# FrameworkGPU_to_MXM.net
KiCad netlist of a schematic drawn in EasyEDA Pro
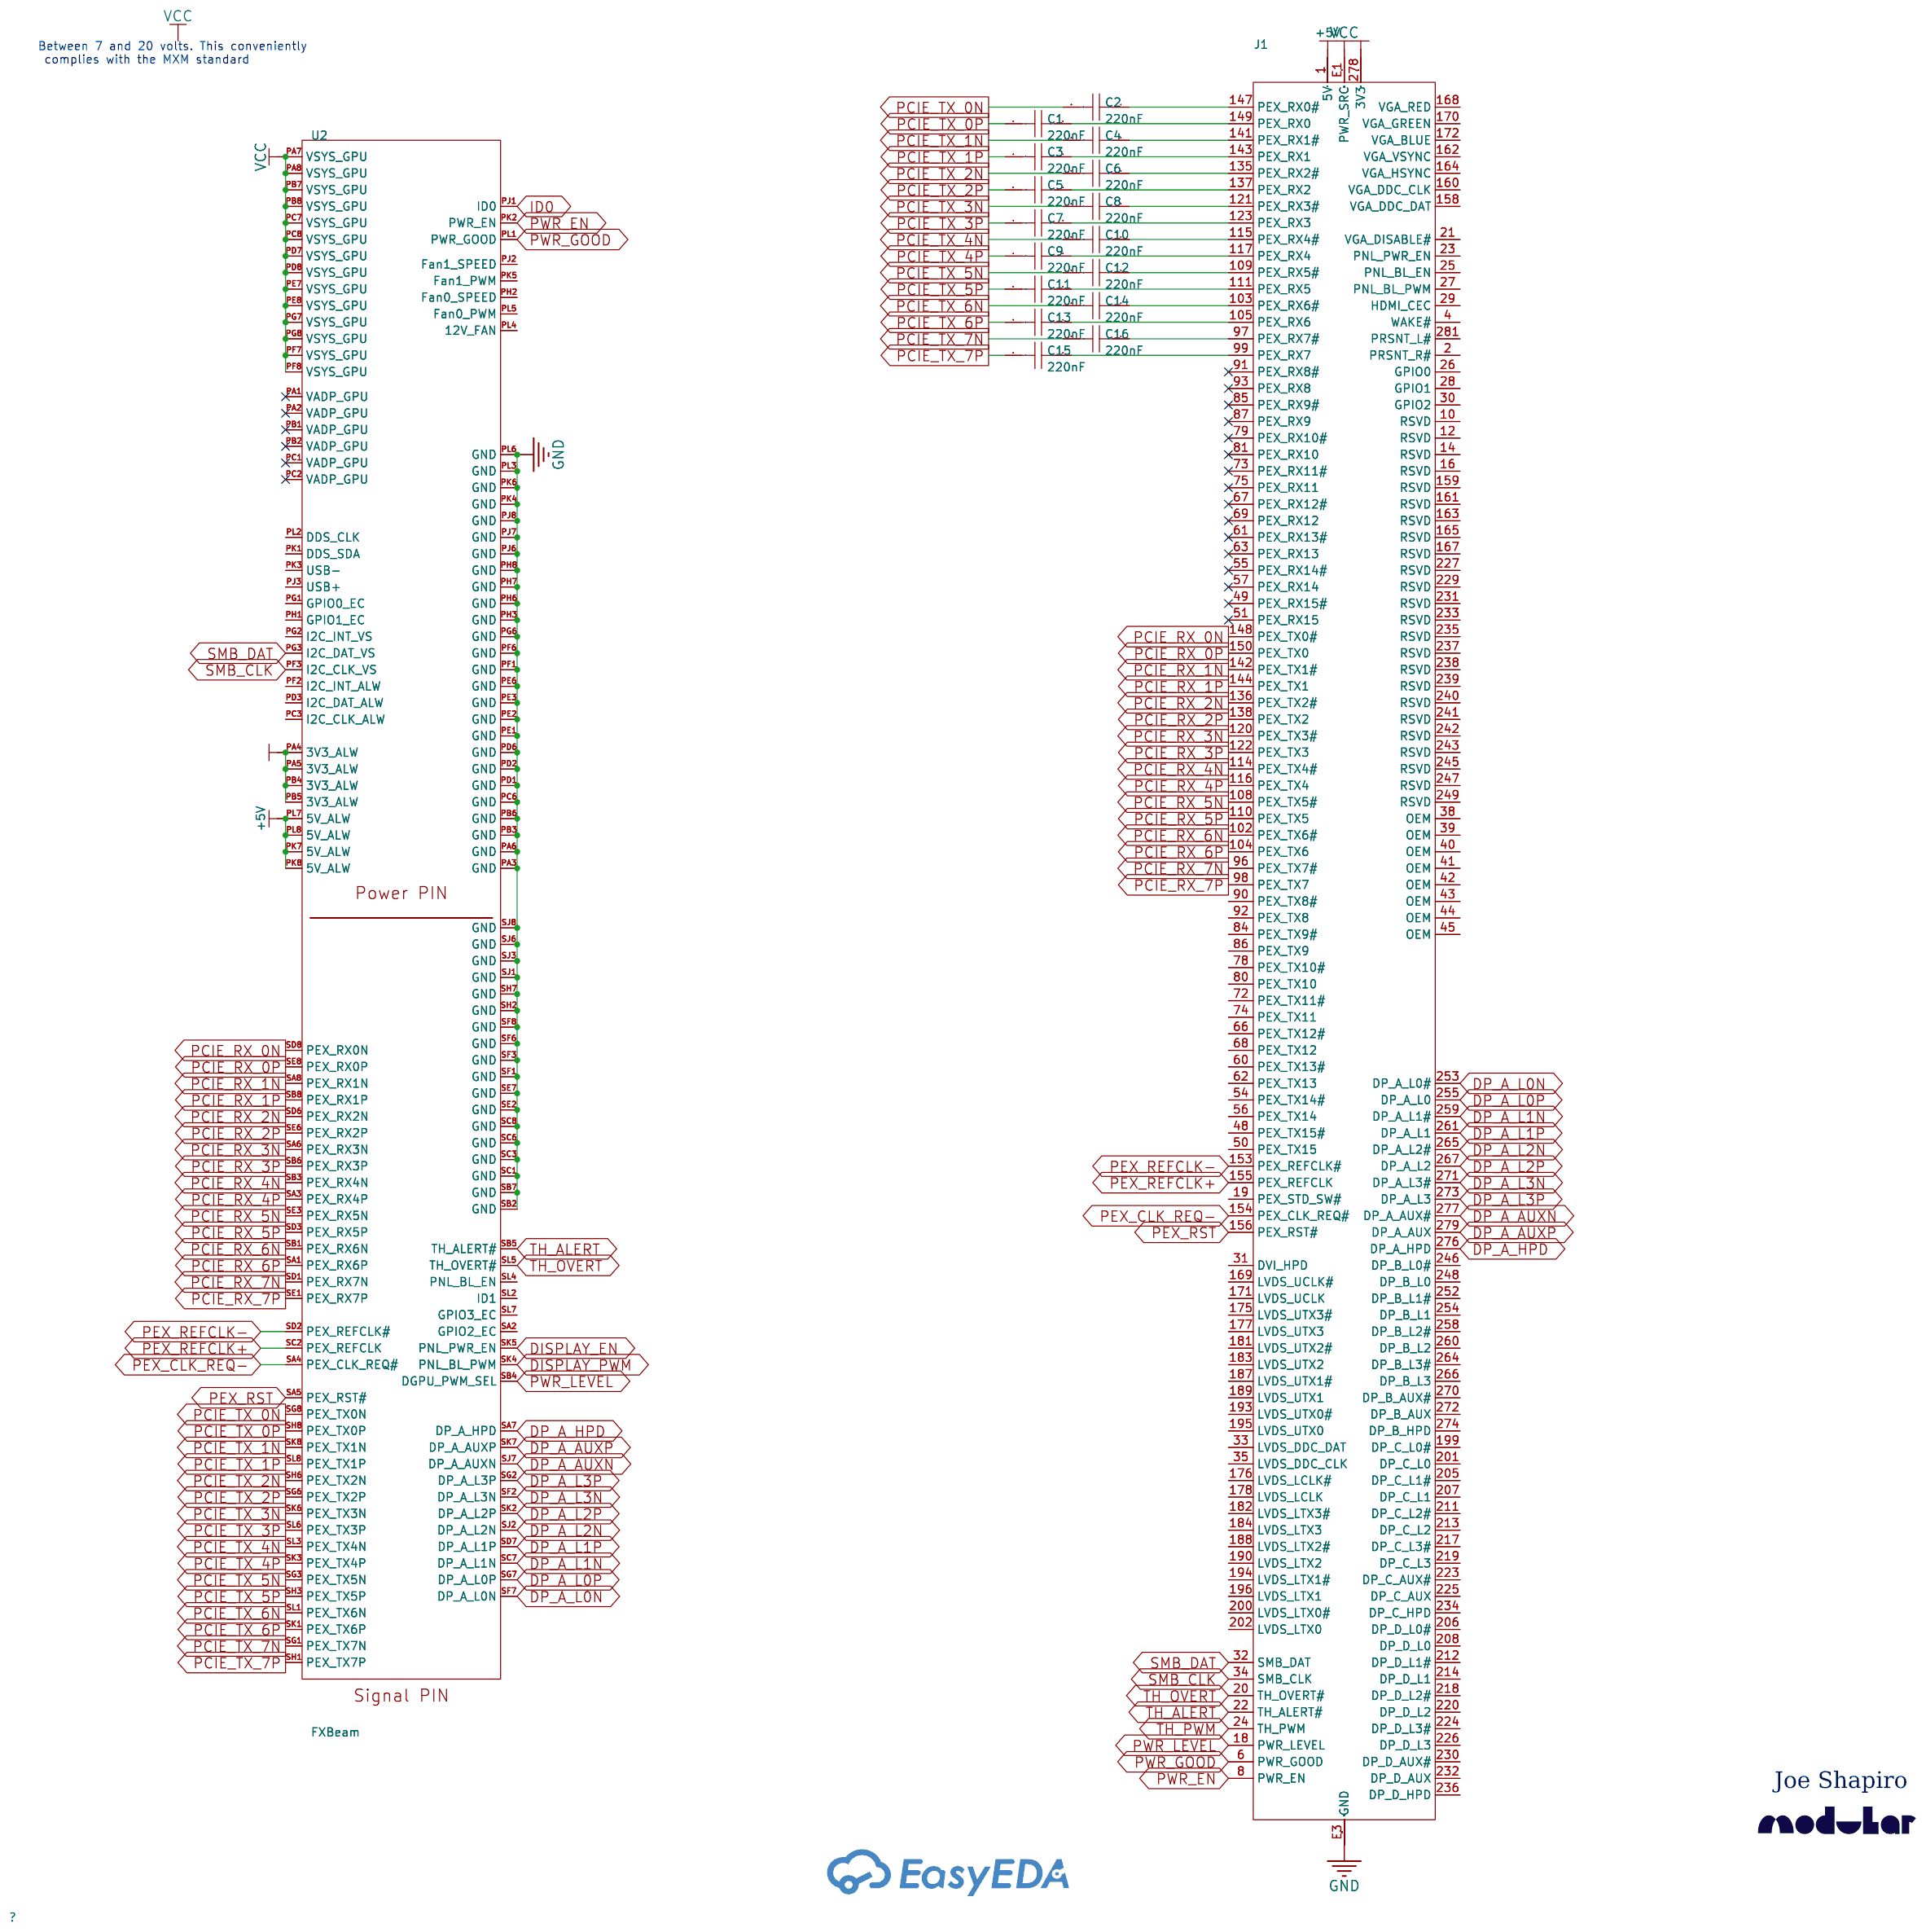
[diagram p0: schematic sheet]

(export (version "E")
  (design (tool "Eeschema 10.0.6"))
  (components
    (comp (ref "C1")
      (value "220nF")
      (footprint "easyedapro:C0603")
      (libsource (lib "easyedapro") (part "CAP"))
    )
    (comp (ref "C2")
      (value "220nF")
      (footprint "easyedapro:C0603")
      (libsource (lib "easyedapro") (part "CAP"))
    )
    (comp (ref "C3")
      (value "220nF")
      (footprint "easyedapro:C0603")
      (libsource (lib "easyedapro") (part "CAP"))
    )
    (comp (ref "C4")
      (value "220nF")
      (footprint "easyedapro:C0603")
      (libsource (lib "easyedapro") (part "CAP"))
    )
    (comp (ref "C5")
      (value "220nF")
      (footprint "easyedapro:C0603")
      (libsource (lib "easyedapro") (part "CAP"))
    )
    (comp (ref "C6")
      (value "220nF")
      (footprint "easyedapro:C0603")
      (libsource (lib "easyedapro") (part "CAP"))
    )
    (comp (ref "C7")
      (value "220nF")
      (footprint "easyedapro:C0603")
      (libsource (lib "easyedapro") (part "CAP"))
    )
    (comp (ref "C8")
      (value "220nF")
      (footprint "easyedapro:C0603")
      (libsource (lib "easyedapro") (part "CAP"))
    )
    (comp (ref "C9")
      (value "220nF")
      (footprint "easyedapro:C0603")
      (libsource (lib "easyedapro") (part "CAP"))
    )
    (comp (ref "C10")
      (value "220nF")
      (footprint "easyedapro:C0603")
      (libsource (lib "easyedapro") (part "CAP"))
    )
    (comp (ref "C11")
      (value "220nF")
      (footprint "easyedapro:C0603")
      (libsource (lib "easyedapro") (part "CAP"))
    )
    (comp (ref "C12")
      (value "220nF")
      (footprint "easyedapro:C0603")
      (libsource (lib "easyedapro") (part "CAP"))
    )
    (comp (ref "C13")
      (value "220nF")
      (footprint "easyedapro:C0603")
      (libsource (lib "easyedapro") (part "CAP"))
    )
    (comp (ref "C14")
      (value "220nF")
      (footprint "easyedapro:C0603")
      (libsource (lib "easyedapro") (part "CAP"))
    )
    (comp (ref "C15")
      (value "220nF")
      (footprint "easyedapro:C0603")
      (libsource (lib "easyedapro") (part "CAP"))
    )
    (comp (ref "C16")
      (value "220nF")
      (footprint "easyedapro:C0603")
      (libsource (lib "easyedapro") (part "CAP"))
    )
    (comp (ref "J1") (value "MXM3.0") (libsource (lib "easyedapro") (part "MXM3.0")))
    (comp (ref "U2") (value "FXBeam") (libsource (lib "easyedapro") (part "FXBeam")))
  )
  (nets
    (net (code "1") (name "+3.3V") (class "Default")
      (node (ref "J1") (pin "278") (pinfunction "3V3_278") (pintype "input"))
      (node (ref "J1") (pin "280") (pinfunction "3V3_280") (pintype "input"))
      (node (ref "U2") (pin "PA4") (pinfunction "3V3_ALW_PA4") (pintype "unspecified"))
      (node (ref "U2") (pin "PA5") (pinfunction "3V3_ALW_PA5") (pintype "unspecified"))
      (node (ref "U2") (pin "PB4") (pinfunction "3V3_ALW_PB4") (pintype "unspecified"))
      (node (ref "U2") (pin "PB5") (pinfunction "3V3_ALW_PB5") (pintype "unspecified"))
    )
    (net (code "2") (name "+5V") (class "Default")
      (node (ref "J1") (pin "1") (pinfunction "5V_1") (pintype "input"))
      (node (ref "J1") (pin "3") (pinfunction "5V_3") (pintype "input"))
      (node (ref "J1") (pin "5") (pinfunction "5V_5") (pintype "input"))
      (node (ref "J1") (pin "7") (pinfunction "5V_7") (pintype "input"))
      (node (ref "J1") (pin "9") (pinfunction "5V_9") (pintype "input"))
      (node (ref "U2") (pin "PK7") (pinfunction "5V_ALW_PK7") (pintype "unspecified"))
      (node (ref "U2") (pin "PK8") (pinfunction "5V_ALW_PK8") (pintype "unspecified"))
      (node (ref "U2") (pin "PL7") (pinfunction "5V_ALW_PL7") (pintype "unspecified"))
      (node (ref "U2") (pin "PL8") (pinfunction "5V_ALW_PL8") (pintype "unspecified"))
    )
    (net (code "3") (name "DISPLAY_EN") (class "Default")
      (node (ref "U2") (pin "SK5") (pinfunction "PNL_PWR_EN_SK5") (pintype "unspecified"))
    )
    (net (code "4") (name "DISPLAY_PWM") (class "Default")
      (node (ref "U2") (pin "SK4") (pinfunction "PNL_BL_PWM_SK4") (pintype "unspecified"))
    )
    (net (code "5") (name "DP_A_AUXN") (class "Default")
      (node (ref "J1") (pin "277") (pinfunction "DP_A_AUX#_277") (pintype "bidirectional"))
      (node (ref "U2") (pin "SJ7") (pinfunction "DP_A_AUXN_SJ7") (pintype "unspecified"))
    )
    (net (code "6") (name "DP_A_AUXP") (class "Default")
      (node (ref "J1") (pin "279") (pinfunction "DP_A_AUX_279") (pintype "bidirectional"))
      (node (ref "U2") (pin "SK7") (pinfunction "DP_A_AUXP_SK7") (pintype "unspecified"))
    )
    (net (code "7") (name "DP_A_HPD") (class "Default")
      (node (ref "J1") (pin "276") (pinfunction "DP_A_HPD_276") (pintype "input"))
      (node (ref "U2") (pin "SA7") (pinfunction "DP_A_HPD_SA7") (pintype "unspecified"))
    )
    (net (code "8") (name "DP_A_L0N") (class "Default")
      (node (ref "J1") (pin "253") (pinfunction "DP_A_L0#_253") (pintype "output"))
      (node (ref "U2") (pin "SF7") (pinfunction "DP_A_L0N_SF7") (pintype "unspecified"))
    )
    (net (code "9") (name "DP_A_L0P") (class "Default")
      (node (ref "J1") (pin "255") (pinfunction "DP_A_L0_255") (pintype "output"))
      (node (ref "U2") (pin "SG7") (pinfunction "DP_A_L0P_SG7") (pintype "unspecified"))
    )
    (net (code "10") (name "DP_A_L1N") (class "Default")
      (node (ref "J1") (pin "259") (pinfunction "DP_A_L1#_259") (pintype "output"))
      (node (ref "U2") (pin "SC7") (pinfunction "DP_A_L1N_SC7") (pintype "unspecified"))
    )
    (net (code "11") (name "DP_A_L1P") (class "Default")
      (node (ref "J1") (pin "261") (pinfunction "DP_A_L1_261") (pintype "output"))
      (node (ref "U2") (pin "SD7") (pinfunction "DP_A_L1P_SD7") (pintype "unspecified"))
    )
    (net (code "12") (name "DP_A_L2N") (class "Default")
      (node (ref "J1") (pin "265") (pinfunction "DP_A_L2#_265") (pintype "output"))
      (node (ref "U2") (pin "SJ2") (pinfunction "DP_A_L2N_SJ2") (pintype "unspecified"))
    )
    (net (code "13") (name "DP_A_L2P") (class "Default")
      (node (ref "J1") (pin "267") (pinfunction "DP_A_L2_267") (pintype "output"))
      (node (ref "U2") (pin "SK2") (pinfunction "DP_A_L2P_SK2") (pintype "unspecified"))
    )
    (net (code "14") (name "DP_A_L3N") (class "Default")
      (node (ref "J1") (pin "271") (pinfunction "DP_A_L3#_271") (pintype "output"))
      (node (ref "U2") (pin "SF2") (pinfunction "DP_A_L3N_SF2") (pintype "unspecified"))
    )
    (net (code "15") (name "DP_A_L3P") (class "Default")
      (node (ref "J1") (pin "273") (pinfunction "DP_A_L3_273") (pintype "output"))
      (node (ref "U2") (pin "SG2") (pinfunction "DP_A_L3P_SG2") (pintype "unspecified"))
    )
    (net (code "16") (name "GND") (class "Default")
      (node (ref "J1") (pin "100") (pinfunction "GND_100") (pintype "input"))
      (node (ref "J1") (pin "101") (pinfunction "GND_101") (pintype "input"))
      (node (ref "J1") (pin "106") (pinfunction "GND_106") (pintype "input"))
      (node (ref "J1") (pin "107") (pinfunction "GND_107") (pintype "input"))
      (node (ref "J1") (pin "11") (pinfunction "GND_11") (pintype "input"))
      (node (ref "J1") (pin "112") (pinfunction "GND_112") (pintype "input"))
      (node (ref "J1") (pin "113") (pinfunction "GND_113") (pintype "input"))
      (node (ref "J1") (pin "118") (pinfunction "GND_118") (pintype "input"))
      (node (ref "J1") (pin "119") (pinfunction "GND_119") (pintype "input"))
      (node (ref "J1") (pin "124") (pinfunction "GND_124") (pintype "input"))
      (node (ref "J1") (pin "125") (pinfunction "GND_125") (pintype "input"))
      (node (ref "J1") (pin "13") (pinfunction "GND_13") (pintype "input"))
      (node (ref "J1") (pin "133") (pinfunction "GND_133") (pintype "input"))
      (node (ref "J1") (pin "134") (pinfunction "GND_134") (pintype "input"))
      (node (ref "J1") (pin "139") (pinfunction "GND_139") (pintype "input"))
      (node (ref "J1") (pin "140") (pinfunction "GND_140") (pintype "input"))
      (node (ref "J1") (pin "145") (pinfunction "GND_145") (pintype "input"))
      (node (ref "J1") (pin "146") (pinfunction "GND_146") (pintype "input"))
      (node (ref "J1") (pin "15") (pinfunction "GND_15") (pintype "input"))
      (node (ref "J1") (pin "151") (pinfunction "GND_151") (pintype "input"))
      (node (ref "J1") (pin "152") (pinfunction "GND_152") (pintype "input"))
      (node (ref "J1") (pin "157") (pinfunction "GND_157") (pintype "input"))
      (node (ref "J1") (pin "166") (pinfunction "GND_166") (pintype "input"))
      (node (ref "J1") (pin "17") (pinfunction "GND_17") (pintype "input"))
      (node (ref "J1") (pin "173") (pinfunction "GND_173") (pintype "input"))
      (node (ref "J1") (pin "174") (pinfunction "GND_174") (pintype "input"))
      (node (ref "J1") (pin "179") (pinfunction "GND_179") (pintype "input"))
      (node (ref "J1") (pin "180") (pinfunction "GND_180") (pintype "input"))
      (node (ref "J1") (pin "185") (pinfunction "GND_185") (pintype "input"))
      (node (ref "J1") (pin "186") (pinfunction "GND_186") (pintype "input"))
      (node (ref "J1") (pin "191") (pinfunction "GND_191") (pintype "input"))
      (node (ref "J1") (pin "192") (pinfunction "GND_192") (pintype "input"))
      (node (ref "J1") (pin "197") (pinfunction "GND_197") (pintype "input"))
      (node (ref "J1") (pin "198") (pinfunction "GND_198") (pintype "input"))
      (node (ref "J1") (pin "203") (pinfunction "GND_203") (pintype "input"))
      (node (ref "J1") (pin "204") (pinfunction "GND_204") (pintype "input"))
      (node (ref "J1") (pin "209") (pinfunction "GND_209") (pintype "input"))
      (node (ref "J1") (pin "210") (pinfunction "GND_210") (pintype "input"))
      (node (ref "J1") (pin "215") (pinfunction "GND_215") (pintype "input"))
      (node (ref "J1") (pin "216") (pinfunction "GND_216") (pintype "input"))
      (node (ref "J1") (pin "221") (pinfunction "GND_221") (pintype "input"))
      (node (ref "J1") (pin "222") (pinfunction "GND_222") (pintype "input"))
      (node (ref "J1") (pin "228") (pinfunction "GND_228") (pintype "input"))
      (node (ref "J1") (pin "244") (pinfunction "GND_244") (pintype "input"))
      (node (ref "J1") (pin "250") (pinfunction "GND_250") (pintype "input"))
      (node (ref "J1") (pin "251") (pinfunction "GND_251") (pintype "input"))
      (node (ref "J1") (pin "256") (pinfunction "GND_256") (pintype "input"))
      (node (ref "J1") (pin "257") (pinfunction "GND_257") (pintype "input"))
      (node (ref "J1") (pin "262") (pinfunction "GND_262") (pintype "input"))
      (node (ref "J1") (pin "263") (pinfunction "GND_263") (pintype "input"))
      (node (ref "J1") (pin "268") (pinfunction "GND_268") (pintype "input"))
      (node (ref "J1") (pin "269") (pinfunction "GND_269") (pintype "input"))
      (node (ref "J1") (pin "275") (pinfunction "GND_275") (pintype "input"))
      (node (ref "J1") (pin "36") (pinfunction "GND_36") (pintype "input"))
      (node (ref "J1") (pin "37") (pinfunction "GND_37") (pintype "input"))
      (node (ref "J1") (pin "46") (pinfunction "GND_46") (pintype "input"))
      (node (ref "J1") (pin "47") (pinfunction "GND_47") (pintype "input"))
      (node (ref "J1") (pin "52") (pinfunction "GND_52") (pintype "input"))
      (node (ref "J1") (pin "53") (pinfunction "GND_53") (pintype "input"))
      (node (ref "J1") (pin "58") (pinfunction "GND_58") (pintype "input"))
      (node (ref "J1") (pin "59") (pinfunction "GND_59") (pintype "input"))
      (node (ref "J1") (pin "64") (pinfunction "GND_64") (pintype "input"))
      (node (ref "J1") (pin "65") (pinfunction "GND_65") (pintype "input"))
      (node (ref "J1") (pin "70") (pinfunction "GND_70") (pintype "input"))
      (node (ref "J1") (pin "71") (pinfunction "GND_71") (pintype "input"))
      (node (ref "J1") (pin "76") (pinfunction "GND_76") (pintype "input"))
      (node (ref "J1") (pin "77") (pinfunction "GND_77") (pintype "input"))
      (node (ref "J1") (pin "82") (pinfunction "GND_82") (pintype "input"))
      (node (ref "J1") (pin "83") (pinfunction "GND_83") (pintype "input"))
      (node (ref "J1") (pin "88") (pinfunction "GND_88") (pintype "input"))
      (node (ref "J1") (pin "89") (pinfunction "GND_89") (pintype "input"))
      (node (ref "J1") (pin "94") (pinfunction "GND_94") (pintype "input"))
      (node (ref "J1") (pin "95") (pinfunction "GND_95") (pintype "input"))
      (node (ref "J1") (pin "E3") (pinfunction "GND_E3") (pintype "input"))
      (node (ref "J1") (pin "E4") (pinfunction "GND_E4") (pintype "input"))
      (node (ref "U2") (pin "PA3") (pinfunction "GND_PA3") (pintype "unspecified"))
      (node (ref "U2") (pin "PA6") (pinfunction "GND_PA6") (pintype "unspecified"))
      (node (ref "U2") (pin "PB3") (pinfunction "GND_PB3") (pintype "unspecified"))
      (node (ref "U2") (pin "PB6") (pinfunction "GND_PB6") (pintype "unspecified"))
      (node (ref "U2") (pin "PC6") (pinfunction "GND_PC6") (pintype "unspecified"))
      (node (ref "U2") (pin "PD1") (pinfunction "GND_PD1") (pintype "unspecified"))
      (node (ref "U2") (pin "PD2") (pinfunction "GND_PD2") (pintype "unspecified"))
      (node (ref "U2") (pin "PD6") (pinfunction "GND_PD6") (pintype "unspecified"))
      (node (ref "U2") (pin "PE1") (pinfunction "GND_PE1") (pintype "unspecified"))
      (node (ref "U2") (pin "PE2") (pinfunction "GND_PE2") (pintype "unspecified"))
      (node (ref "U2") (pin "PE3") (pinfunction "GND_PE3") (pintype "unspecified"))
      (node (ref "U2") (pin "PE6") (pinfunction "GND_PE6") (pintype "unspecified"))
      (node (ref "U2") (pin "PF1") (pinfunction "GND_PF1") (pintype "unspecified"))
      (node (ref "U2") (pin "PF6") (pinfunction "GND_PF6") (pintype "unspecified"))
      (node (ref "U2") (pin "PG6") (pinfunction "GND_PG6") (pintype "unspecified"))
      (node (ref "U2") (pin "PH3") (pinfunction "GND_PH3") (pintype "unspecified"))
      (node (ref "U2") (pin "PH6") (pinfunction "GND_PH6") (pintype "unspecified"))
      (node (ref "U2") (pin "PH7") (pinfunction "GND_PH7") (pintype "unspecified"))
      (node (ref "U2") (pin "PH8") (pinfunction "GND_PH8") (pintype "unspecified"))
      (node (ref "U2") (pin "PJ6") (pinfunction "GND_PJ6") (pintype "unspecified"))
      (node (ref "U2") (pin "PJ7") (pinfunction "GND_PJ7") (pintype "unspecified"))
      (node (ref "U2") (pin "PJ8") (pinfunction "GND_PJ8") (pintype "unspecified"))
      (node (ref "U2") (pin "PK4") (pinfunction "GND_PK4") (pintype "unspecified"))
      (node (ref "U2") (pin "PK6") (pinfunction "GND_PK6") (pintype "unspecified"))
      (node (ref "U2") (pin "PL3") (pinfunction "GND_PL3") (pintype "unspecified"))
      (node (ref "U2") (pin "PL6") (pinfunction "GND_PL6") (pintype "unspecified"))
      (node (ref "U2") (pin "SB2") (pinfunction "GND_SB2") (pintype "unspecified"))
      (node (ref "U2") (pin "SB7") (pinfunction "GND_SB7") (pintype "unspecified"))
      (node (ref "U2") (pin "SC1") (pinfunction "GND_SC1") (pintype "unspecified"))
      (node (ref "U2") (pin "SC3") (pinfunction "GND_SC3") (pintype "unspecified"))
      (node (ref "U2") (pin "SC6") (pinfunction "GND_SC6") (pintype "unspecified"))
      (node (ref "U2") (pin "SC8") (pinfunction "GND_SC8") (pintype "unspecified"))
      (node (ref "U2") (pin "SE2") (pinfunction "GND_SE2") (pintype "unspecified"))
      (node (ref "U2") (pin "SE7") (pinfunction "GND_SE7") (pintype "unspecified"))
      (node (ref "U2") (pin "SF1") (pinfunction "GND_SF1") (pintype "unspecified"))
      (node (ref "U2") (pin "SF3") (pinfunction "GND_SF3") (pintype "unspecified"))
      (node (ref "U2") (pin "SF6") (pinfunction "GND_SF6") (pintype "unspecified"))
      (node (ref "U2") (pin "SF8") (pinfunction "GND_SF8") (pintype "unspecified"))
      (node (ref "U2") (pin "SH2") (pinfunction "GND_SH2") (pintype "unspecified"))
      (node (ref "U2") (pin "SH7") (pinfunction "GND_SH7") (pintype "unspecified"))
      (node (ref "U2") (pin "SJ1") (pinfunction "GND_SJ1") (pintype "unspecified"))
      (node (ref "U2") (pin "SJ3") (pinfunction "GND_SJ3") (pintype "unspecified"))
      (node (ref "U2") (pin "SJ6") (pinfunction "GND_SJ6") (pintype "unspecified"))
      (node (ref "U2") (pin "SJ8") (pinfunction "GND_SJ8") (pintype "unspecified"))
    )
    (net (code "17") (name "ID0") (class "Default")
      (node (ref "U2") (pin "PJ1") (pinfunction "ID0_PJ1") (pintype "output"))
    )
    (net (code "18") (name "Net-(J1-PEX_RX0#)") (class "Default")
      (node (ref "C2") (pin "1") (pinfunction "1_1") (pintype "input"))
      (node (ref "J1") (pin "147") (pinfunction "PEX_RX0#_147") (pintype "output"))
    )
    (net (code "19") (name "Net-(J1-PEX_RX0)") (class "Default")
      (node (ref "C1") (pin "1") (pinfunction "1_1") (pintype "input"))
      (node (ref "J1") (pin "149") (pinfunction "PEX_RX0_149") (pintype "output"))
    )
    (net (code "20") (name "Net-(J1-PEX_RX1#)") (class "Default")
      (node (ref "C4") (pin "1") (pinfunction "1_1") (pintype "input"))
      (node (ref "J1") (pin "141") (pinfunction "PEX_RX1#_141") (pintype "output"))
    )
    (net (code "21") (name "Net-(J1-PEX_RX1)") (class "Default")
      (node (ref "C3") (pin "1") (pinfunction "1_1") (pintype "input"))
      (node (ref "J1") (pin "143") (pinfunction "PEX_RX1_143") (pintype "output"))
    )
    (net (code "22") (name "Net-(J1-PEX_RX2#)") (class "Default")
      (node (ref "C6") (pin "1") (pinfunction "1_1") (pintype "input"))
      (node (ref "J1") (pin "135") (pinfunction "PEX_RX2#_135") (pintype "output"))
    )
    (net (code "23") (name "Net-(J1-PEX_RX2)") (class "Default")
      (node (ref "C5") (pin "1") (pinfunction "1_1") (pintype "input"))
      (node (ref "J1") (pin "137") (pinfunction "PEX_RX2_137") (pintype "output"))
    )
    (net (code "24") (name "Net-(J1-PEX_RX3#)") (class "Default")
      (node (ref "C8") (pin "1") (pinfunction "1_1") (pintype "input"))
      (node (ref "J1") (pin "121") (pinfunction "PEX_RX3#_121") (pintype "output"))
    )
    (net (code "25") (name "Net-(J1-PEX_RX3)") (class "Default")
      (node (ref "C7") (pin "1") (pinfunction "1_1") (pintype "input"))
      (node (ref "J1") (pin "123") (pinfunction "PEX_RX3_123") (pintype "output"))
    )
    (net (code "26") (name "Net-(J1-PEX_RX4#)") (class "Default")
      (node (ref "C10") (pin "1") (pinfunction "1_1") (pintype "input"))
      (node (ref "J1") (pin "115") (pinfunction "PEX_RX4#_115") (pintype "output"))
    )
    (net (code "27") (name "Net-(J1-PEX_RX4)") (class "Default")
      (node (ref "C9") (pin "1") (pinfunction "1_1") (pintype "input"))
      (node (ref "J1") (pin "117") (pinfunction "PEX_RX4_117") (pintype "output"))
    )
    (net (code "28") (name "Net-(J1-PEX_RX5#)") (class "Default")
      (node (ref "C12") (pin "1") (pinfunction "1_1") (pintype "input"))
      (node (ref "J1") (pin "109") (pinfunction "PEX_RX5#_109") (pintype "output"))
    )
    (net (code "29") (name "Net-(J1-PEX_RX5)") (class "Default")
      (node (ref "C11") (pin "1") (pinfunction "1_1") (pintype "input"))
      (node (ref "J1") (pin "111") (pinfunction "PEX_RX5_111") (pintype "output"))
    )
    (net (code "30") (name "Net-(J1-PEX_RX6#)") (class "Default")
      (node (ref "C14") (pin "1") (pinfunction "1_1") (pintype "input"))
      (node (ref "J1") (pin "103") (pinfunction "PEX_RX6#_103") (pintype "output"))
    )
    (net (code "31") (name "Net-(J1-PEX_RX6)") (class "Default")
      (node (ref "C13") (pin "1") (pinfunction "1_1") (pintype "input"))
      (node (ref "J1") (pin "105") (pinfunction "PEX_RX6_105") (pintype "output"))
    )
    (net (code "32") (name "Net-(J1-PEX_RX7#)") (class "Default")
      (node (ref "C16") (pin "1") (pinfunction "1_1") (pintype "input"))
      (node (ref "J1") (pin "97") (pinfunction "PEX_RX7#_97") (pintype "output"))
    )
    (net (code "33") (name "Net-(J1-PEX_RX7)") (class "Default")
      (node (ref "C15") (pin "1") (pinfunction "1_1") (pintype "input"))
      (node (ref "J1") (pin "99") (pinfunction "PEX_RX7_99") (pintype "output"))
    )
    (net (code "34") (name "PCIE_RX_0N") (class "Default")
      (node (ref "J1") (pin "148") (pinfunction "PEX_TX0#_148") (pintype "input"))
      (node (ref "U2") (pin "SD8") (pinfunction "PEX_RX0N_SD8") (pintype "unspecified"))
    )
    (net (code "35") (name "PCIE_RX_0P") (class "Default")
      (node (ref "J1") (pin "150") (pinfunction "PEX_TX0_150") (pintype "input"))
      (node (ref "U2") (pin "SE8") (pinfunction "PEX_RX0P_SE8") (pintype "unspecified"))
    )
    (net (code "36") (name "PCIE_RX_1N") (class "Default")
      (node (ref "J1") (pin "142") (pinfunction "PEX_TX1#_142") (pintype "input"))
      (node (ref "U2") (pin "SA8") (pinfunction "PEX_RX1N_SA8") (pintype "unspecified"))
    )
    (net (code "37") (name "PCIE_RX_1P") (class "Default")
      (node (ref "J1") (pin "144") (pinfunction "PEX_TX1_144") (pintype "input"))
      (node (ref "U2") (pin "SB8") (pinfunction "PEX_RX1P_SB8") (pintype "unspecified"))
    )
    (net (code "38") (name "PCIE_RX_2N") (class "Default")
      (node (ref "J1") (pin "136") (pinfunction "PEX_TX2#_136") (pintype "input"))
      (node (ref "U2") (pin "SD6") (pinfunction "PEX_RX2N_SD6") (pintype "unspecified"))
    )
    (net (code "39") (name "PCIE_RX_2P") (class "Default")
      (node (ref "J1") (pin "138") (pinfunction "PEX_TX2_138") (pintype "input"))
      (node (ref "U2") (pin "SE6") (pinfunction "PEX_RX2P_SE6") (pintype "unspecified"))
    )
    (net (code "40") (name "PCIE_RX_3N") (class "Default")
      (node (ref "J1") (pin "120") (pinfunction "PEX_TX3#_120") (pintype "input"))
      (node (ref "U2") (pin "SA6") (pinfunction "PEX_RX3N_SA6") (pintype "unspecified"))
    )
    (net (code "41") (name "PCIE_RX_3P") (class "Default")
      (node (ref "J1") (pin "122") (pinfunction "PEX_TX3_122") (pintype "input"))
      (node (ref "U2") (pin "SB6") (pinfunction "PEX_RX3P_SB6") (pintype "unspecified"))
    )
    (net (code "42") (name "PCIE_RX_4N") (class "Default")
      (node (ref "J1") (pin "114") (pinfunction "PEX_TX4#_114") (pintype "input"))
      (node (ref "U2") (pin "SB3") (pinfunction "PEX_RX4N_SB3") (pintype "unspecified"))
    )
    (net (code "43") (name "PCIE_RX_4P") (class "Default")
      (node (ref "J1") (pin "116") (pinfunction "PEX_TX4_116") (pintype "input"))
      (node (ref "U2") (pin "SA3") (pinfunction "PEX_RX4P_SA3") (pintype "unspecified"))
    )
    (net (code "44") (name "PCIE_RX_5N") (class "Default")
      (node (ref "J1") (pin "108") (pinfunction "PEX_TX5#_108") (pintype "input"))
      (node (ref "U2") (pin "SE3") (pinfunction "PEX_RX5N_SE3") (pintype "unspecified"))
    )
    (net (code "45") (name "PCIE_RX_5P") (class "Default")
      (node (ref "J1") (pin "110") (pinfunction "PEX_TX5_110") (pintype "input"))
      (node (ref "U2") (pin "SD3") (pinfunction "PEX_RX5P_SD3") (pintype "unspecified"))
    )
    (net (code "46") (name "PCIE_RX_6N") (class "Default")
      (node (ref "J1") (pin "102") (pinfunction "PEX_TX6#_102") (pintype "input"))
      (node (ref "U2") (pin "SB1") (pinfunction "PEX_RX6N_SB1") (pintype "unspecified"))
    )
    (net (code "47") (name "PCIE_RX_6P") (class "Default")
      (node (ref "J1") (pin "104") (pinfunction "PEX_TX6_104") (pintype "input"))
      (node (ref "U2") (pin "SA1") (pinfunction "PEX_RX6P_SA1") (pintype "unspecified"))
    )
    (net (code "48") (name "PCIE_RX_7N") (class "Default")
      (node (ref "J1") (pin "96") (pinfunction "PEX_TX7#_96") (pintype "input"))
      (node (ref "U2") (pin "SD1") (pinfunction "PEX_RX7N_SD1") (pintype "unspecified"))
    )
    (net (code "49") (name "PCIE_RX_7P") (class "Default")
      (node (ref "J1") (pin "98") (pinfunction "PEX_TX7_98") (pintype "input"))
      (node (ref "U2") (pin "SE1") (pinfunction "PEX_RX7P_SE1") (pintype "unspecified"))
    )
    (net (code "50") (name "PCIE_TX_0N") (class "Default")
      (node (ref "C2") (pin "2") (pinfunction "2_2") (pintype "input"))
      (node (ref "U2") (pin "SG8") (pinfunction "PEX_TX0N_SG8") (pintype "unspecified"))
    )
    (net (code "51") (name "PCIE_TX_0P") (class "Default")
      (node (ref "C1") (pin "2") (pinfunction "2_2") (pintype "input"))
      (node (ref "U2") (pin "SH8") (pinfunction "PEX_TX0P_SH8") (pintype "unspecified"))
    )
    (net (code "52") (name "PCIE_TX_1N") (class "Default")
      (node (ref "C4") (pin "2") (pinfunction "2_2") (pintype "input"))
      (node (ref "U2") (pin "SK8") (pinfunction "PEX_TX1N_SK8") (pintype "unspecified"))
    )
    (net (code "53") (name "PCIE_TX_1P") (class "Default")
      (node (ref "C3") (pin "2") (pinfunction "2_2") (pintype "input"))
      (node (ref "U2") (pin "SL8") (pinfunction "PEX_TX1P_SL8") (pintype "unspecified"))
    )
    (net (code "54") (name "PCIE_TX_2N") (class "Default")
      (node (ref "C6") (pin "2") (pinfunction "2_2") (pintype "input"))
      (node (ref "U2") (pin "SH6") (pinfunction "PEX_TX2N_SH6") (pintype "unspecified"))
    )
    (net (code "55") (name "PCIE_TX_2P") (class "Default")
      (node (ref "C5") (pin "2") (pinfunction "2_2") (pintype "input"))
      (node (ref "U2") (pin "SG6") (pinfunction "PEX_TX2P_SG6") (pintype "unspecified"))
    )
    (net (code "56") (name "PCIE_TX_3N") (class "Default")
      (node (ref "C8") (pin "2") (pinfunction "2_2") (pintype "input"))
      (node (ref "U2") (pin "SK6") (pinfunction "PEX_TX3N_SK6") (pintype "unspecified"))
    )
    (net (code "57") (name "PCIE_TX_3P") (class "Default")
      (node (ref "C7") (pin "2") (pinfunction "2_2") (pintype "input"))
      (node (ref "U2") (pin "SL6") (pinfunction "PEX_TX3P_SL6") (pintype "unspecified"))
    )
    (net (code "58") (name "PCIE_TX_4N") (class "Default")
      (node (ref "C10") (pin "2") (pinfunction "2_2") (pintype "input"))
      (node (ref "U2") (pin "SL3") (pinfunction "PEX_TX4N_SL3") (pintype "unspecified"))
    )
    (net (code "59") (name "PCIE_TX_4P") (class "Default")
      (node (ref "C9") (pin "2") (pinfunction "2_2") (pintype "input"))
      (node (ref "U2") (pin "SK3") (pinfunction "PEX_TX4P_SK3") (pintype "unspecified"))
    )
    (net (code "60") (name "PCIE_TX_5N") (class "Default")
      (node (ref "C12") (pin "2") (pinfunction "2_2") (pintype "input"))
      (node (ref "U2") (pin "SG3") (pinfunction "PEX_TX5N_SG3") (pintype "unspecified"))
    )
    (net (code "61") (name "PCIE_TX_5P") (class "Default")
      (node (ref "C11") (pin "2") (pinfunction "2_2") (pintype "input"))
      (node (ref "U2") (pin "SH3") (pinfunction "PEX_TX5P_SH3") (pintype "unspecified"))
    )
    (net (code "62") (name "PCIE_TX_6N") (class "Default")
      (node (ref "C14") (pin "2") (pinfunction "2_2") (pintype "input"))
      (node (ref "U2") (pin "SL1") (pinfunction "PEX_TX6N_SL1") (pintype "unspecified"))
    )
    (net (code "63") (name "PCIE_TX_6P") (class "Default")
      (node (ref "C13") (pin "2") (pinfunction "2_2") (pintype "input"))
      (node (ref "U2") (pin "SK1") (pinfunction "PEX_TX6P_SK1") (pintype "unspecified"))
    )
    (net (code "64") (name "PCIE_TX_7N") (class "Default")
      (node (ref "C16") (pin "2") (pinfunction "2_2") (pintype "input"))
      (node (ref "U2") (pin "SG1") (pinfunction "PEX_TX7N_SG1") (pintype "unspecified"))
    )
    (net (code "65") (name "PCIE_TX_7P") (class "Default")
      (node (ref "C15") (pin "2") (pinfunction "2_2") (pintype "input"))
      (node (ref "U2") (pin "SH1") (pinfunction "PEX_TX7P_SH1") (pintype "unspecified"))
    )
    (net (code "66") (name "PEX_CLK_REQ-") (class "Default")
      (node (ref "J1") (pin "154") (pinfunction "PEX_CLK_REQ#_154") (pintype "output"))
      (node (ref "U2") (pin "SA4") (pinfunction "PEX_CLK_REQ#_SA4") (pintype "unspecified"))
    )
    (net (code "67") (name "PEX_REFCLK+") (class "Default")
      (node (ref "J1") (pin "155") (pinfunction "PEX_REFCLK_155") (pintype "input"))
      (node (ref "U2") (pin "SC2") (pinfunction "PEX_REFCLK_SC2") (pintype "unspecified"))
    )
    (net (code "68") (name "PEX_REFCLK-") (class "Default")
      (node (ref "J1") (pin "153") (pinfunction "PEX_REFCLK#_153") (pintype "input"))
      (node (ref "U2") (pin "SD2") (pinfunction "PEX_REFCLK#_SD2") (pintype "unspecified"))
    )
    (net (code "69") (name "PEX_RST") (class "Default")
      (node (ref "J1") (pin "156") (pinfunction "PEX_RST#_156") (pintype "input"))
      (node (ref "U2") (pin "SA5") (pinfunction "PEX_RST#_SA5") (pintype "unspecified"))
    )
    (net (code "70") (name "PWR_EN") (class "Default")
      (node (ref "J1") (pin "8") (pinfunction "PWR_EN_8") (pintype "input"))
      (node (ref "U2") (pin "PK2") (pinfunction "PWR_EN_PK2") (pintype "input"))
    )
    (net (code "71") (name "PWR_GOOD") (class "Default")
      (node (ref "J1") (pin "6") (pinfunction "PWR_GOOD_6") (pintype "output"))
      (node (ref "U2") (pin "PL1") (pinfunction "PWR_GOOD_PL1") (pintype "output"))
    )
    (net (code "72") (name "PWR_LEVEL") (class "Default")
      (node (ref "J1") (pin "18") (pinfunction "PWR_LEVEL_18") (pintype "input"))
      (node (ref "U2") (pin "SB4") (pinfunction "DGPU_PWM_SEL_SB4") (pintype "unspecified"))
    )
    (net (code "73") (name "SMB_CLK") (class "Default")
      (node (ref "J1") (pin "34") (pinfunction "SMB_CLK_34") (pintype "input"))
      (node (ref "U2") (pin "PF3") (pinfunction "I2C_CLK_VS_PF3") (pintype "bidirectional"))
    )
    (net (code "74") (name "SMB_DAT") (class "Default")
      (node (ref "J1") (pin "32") (pinfunction "SMB_DAT_32") (pintype "bidirectional"))
      (node (ref "U2") (pin "PG3") (pinfunction "I2C_DAT_VS_PG3") (pintype "unspecified"))
    )
    (net (code "75") (name "TH_ALERT") (class "Default")
      (node (ref "J1") (pin "22") (pinfunction "TH_ALERT#_22") (pintype "bidirectional"))
      (node (ref "U2") (pin "SB5") (pinfunction "TH_ALERT#_SB5") (pintype "unspecified"))
    )
    (net (code "76") (name "TH_OVERT") (class "Default")
      (node (ref "J1") (pin "20") (pinfunction "TH_OVERT#_20") (pintype "output"))
      (node (ref "U2") (pin "SL5") (pinfunction "TH_OVERT#_SL5") (pintype "unspecified"))
    )
    (net (code "77") (name "TH_PWM") (class "Default")
      (node (ref "J1") (pin "24") (pinfunction "TH_PWM_24") (pintype "output"))
    )
    (net (code "78") (name "VCC") (class "Default")
      (node (ref "J1") (pin "E1") (pinfunction "PWR_SRC_E1") (pintype "input"))
      (node (ref "J1") (pin "E2") (pinfunction "PWR_SRC_E2") (pintype "input"))
      (node (ref "U2") (pin "PA7") (pinfunction "VSYS_GPU_PA7") (pintype "unspecified"))
      (node (ref "U2") (pin "PA8") (pinfunction "VSYS_GPU_PA8") (pintype "unspecified"))
      (node (ref "U2") (pin "PB7") (pinfunction "VSYS_GPU_PB7") (pintype "unspecified"))
      (node (ref "U2") (pin "PB8") (pinfunction "VSYS_GPU_PB8") (pintype "unspecified"))
      (node (ref "U2") (pin "PC7") (pinfunction "VSYS_GPU_PC7") (pintype "unspecified"))
      (node (ref "U2") (pin "PC8") (pinfunction "VSYS_GPU_PC8") (pintype "unspecified"))
      (node (ref "U2") (pin "PD7") (pinfunction "VSYS_GPU_PD7") (pintype "unspecified"))
      (node (ref "U2") (pin "PD8") (pinfunction "VSYS_GPU_PD8") (pintype "unspecified"))
      (node (ref "U2") (pin "PE7") (pinfunction "VSYS_GPU_PE7") (pintype "unspecified"))
      (node (ref "U2") (pin "PE8") (pinfunction "VSYS_GPU_PE8") (pintype "unspecified"))
      (node (ref "U2") (pin "PF7") (pinfunction "VSYS_GPU_PF7") (pintype "unspecified"))
      (node (ref "U2") (pin "PF8") (pinfunction "VSYS_GPU_PF8") (pintype "unspecified"))
      (node (ref "U2") (pin "PG7") (pinfunction "VSYS_GPU_PG7") (pintype "unspecified"))
      (node (ref "U2") (pin "PG8") (pinfunction "VSYS_GPU_PG8") (pintype "unspecified"))
    )
    (net (code "79") (name "unconnected-(J1-DP_B_AUX#-Pad270)") (class "Default")
      (node (ref "J1") (pin "270") (pinfunction "DP_B_AUX#_270") (pintype "bidirectional"))
    )
    (net (code "80") (name "unconnected-(J1-DP_B_AUX-Pad272)") (class "Default")
      (node (ref "J1") (pin "272") (pinfunction "DP_B_AUX_272") (pintype "bidirectional"))
    )
    (net (code "81") (name "unconnected-(J1-DP_B_HPD-Pad274)") (class "Default")
      (node (ref "J1") (pin "274") (pinfunction "DP_B_HPD_274") (pintype "input"))
    )
    (net (code "82") (name "unconnected-(J1-DP_B_L0#-Pad246)") (class "Default")
      (node (ref "J1") (pin "246") (pinfunction "DP_B_L0#_246") (pintype "output"))
    )
    (net (code "83") (name "unconnected-(J1-DP_B_L0-Pad248)") (class "Default")
      (node (ref "J1") (pin "248") (pinfunction "DP_B_L0_248") (pintype "output"))
    )
    (net (code "84") (name "unconnected-(J1-DP_B_L1#-Pad252)") (class "Default")
      (node (ref "J1") (pin "252") (pinfunction "DP_B_L1#_252") (pintype "output"))
    )
    (net (code "85") (name "unconnected-(J1-DP_B_L1-Pad254)") (class "Default")
      (node (ref "J1") (pin "254") (pinfunction "DP_B_L1_254") (pintype "output"))
    )
    (net (code "86") (name "unconnected-(J1-DP_B_L2#-Pad258)") (class "Default")
      (node (ref "J1") (pin "258") (pinfunction "DP_B_L2#_258") (pintype "output"))
    )
    (net (code "87") (name "unconnected-(J1-DP_B_L2-Pad260)") (class "Default")
      (node (ref "J1") (pin "260") (pinfunction "DP_B_L2_260") (pintype "output"))
    )
    (net (code "88") (name "unconnected-(J1-DP_B_L3#-Pad264)") (class "Default")
      (node (ref "J1") (pin "264") (pinfunction "DP_B_L3#_264") (pintype "output"))
    )
    (net (code "89") (name "unconnected-(J1-DP_B_L3-Pad266)") (class "Default")
      (node (ref "J1") (pin "266") (pinfunction "DP_B_L3_266") (pintype "output"))
    )
    (net (code "90") (name "unconnected-(J1-DP_C_AUX#-Pad223)") (class "Default")
      (node (ref "J1") (pin "223") (pinfunction "DP_C_AUX#_223") (pintype "bidirectional"))
    )
    (net (code "91") (name "unconnected-(J1-DP_C_AUX-Pad225)") (class "Default")
      (node (ref "J1") (pin "225") (pinfunction "DP_C_AUX_225") (pintype "bidirectional"))
    )
    (net (code "92") (name "unconnected-(J1-DP_C_HPD-Pad234)") (class "Default")
      (node (ref "J1") (pin "234") (pinfunction "DP_C_HPD_234") (pintype "input"))
    )
    (net (code "93") (name "unconnected-(J1-DP_C_L0#-Pad199)") (class "Default")
      (node (ref "J1") (pin "199") (pinfunction "DP_C_L0#_199") (pintype "output"))
    )
    (net (code "94") (name "unconnected-(J1-DP_C_L0-Pad201)") (class "Default")
      (node (ref "J1") (pin "201") (pinfunction "DP_C_L0_201") (pintype "output"))
    )
    (net (code "95") (name "unconnected-(J1-DP_C_L1#-Pad205)") (class "Default")
      (node (ref "J1") (pin "205") (pinfunction "DP_C_L1#_205") (pintype "output"))
    )
    (net (code "96") (name "unconnected-(J1-DP_C_L1-Pad207)") (class "Default")
      (node (ref "J1") (pin "207") (pinfunction "DP_C_L1_207") (pintype "output"))
    )
    (net (code "97") (name "unconnected-(J1-DP_C_L2#-Pad211)") (class "Default")
      (node (ref "J1") (pin "211") (pinfunction "DP_C_L2#_211") (pintype "output"))
    )
    (net (code "98") (name "unconnected-(J1-DP_C_L2-Pad213)") (class "Default")
      (node (ref "J1") (pin "213") (pinfunction "DP_C_L2_213") (pintype "output"))
    )
    (net (code "99") (name "unconnected-(J1-DP_C_L3#-Pad217)") (class "Default")
      (node (ref "J1") (pin "217") (pinfunction "DP_C_L3#_217") (pintype "output"))
    )
    (net (code "100") (name "unconnected-(J1-DP_C_L3-Pad219)") (class "Default")
      (node (ref "J1") (pin "219") (pinfunction "DP_C_L3_219") (pintype "output"))
    )
    (net (code "101") (name "unconnected-(J1-DP_D_AUX#-Pad230)") (class "Default")
      (node (ref "J1") (pin "230") (pinfunction "DP_D_AUX#_230") (pintype "bidirectional"))
    )
    (net (code "102") (name "unconnected-(J1-DP_D_AUX-Pad232)") (class "Default")
      (node (ref "J1") (pin "232") (pinfunction "DP_D_AUX_232") (pintype "bidirectional"))
    )
    (net (code "103") (name "unconnected-(J1-DP_D_HPD-Pad236)") (class "Default")
      (node (ref "J1") (pin "236") (pinfunction "DP_D_HPD_236") (pintype "input"))
    )
    (net (code "104") (name "unconnected-(J1-DP_D_L0#-Pad206)") (class "Default")
      (node (ref "J1") (pin "206") (pinfunction "DP_D_L0#_206") (pintype "output"))
    )
    (net (code "105") (name "unconnected-(J1-DP_D_L0-Pad208)") (class "Default")
      (node (ref "J1") (pin "208") (pinfunction "DP_D_L0_208") (pintype "output"))
    )
    (net (code "106") (name "unconnected-(J1-DP_D_L1#-Pad212)") (class "Default")
      (node (ref "J1") (pin "212") (pinfunction "DP_D_L1#_212") (pintype "output"))
    )
    (net (code "107") (name "unconnected-(J1-DP_D_L1-Pad214)") (class "Default")
      (node (ref "J1") (pin "214") (pinfunction "DP_D_L1_214") (pintype "output"))
    )
    (net (code "108") (name "unconnected-(J1-DP_D_L2#-Pad218)") (class "Default")
      (node (ref "J1") (pin "218") (pinfunction "DP_D_L2#_218") (pintype "output"))
    )
    (net (code "109") (name "unconnected-(J1-DP_D_L2-Pad220)") (class "Default")
      (node (ref "J1") (pin "220") (pinfunction "DP_D_L2_220") (pintype "output"))
    )
    (net (code "110") (name "unconnected-(J1-DP_D_L3#-Pad224)") (class "Default")
      (node (ref "J1") (pin "224") (pinfunction "DP_D_L3#_224") (pintype "output"))
    )
    (net (code "111") (name "unconnected-(J1-DP_D_L3-Pad226)") (class "Default")
      (node (ref "J1") (pin "226") (pinfunction "DP_D_L3_226") (pintype "output"))
    )
    (net (code "112") (name "unconnected-(J1-DVI_HPD-Pad31)") (class "Default")
      (node (ref "J1") (pin "31") (pinfunction "DVI_HPD_31") (pintype "input"))
    )
    (net (code "113") (name "unconnected-(J1-GPIO0-Pad26)") (class "Default")
      (node (ref "J1") (pin "26") (pinfunction "GPIO0_26") (pintype "bidirectional"))
    )
    (net (code "114") (name "unconnected-(J1-GPIO1-Pad28)") (class "Default")
      (node (ref "J1") (pin "28") (pinfunction "GPIO1_28") (pintype "bidirectional"))
    )
    (net (code "115") (name "unconnected-(J1-GPIO2-Pad30)") (class "Default")
      (node (ref "J1") (pin "30") (pinfunction "GPIO2_30") (pintype "bidirectional"))
    )
    (net (code "116") (name "unconnected-(J1-HDMI_CEC-Pad29)") (class "Default")
      (node (ref "J1") (pin "29") (pinfunction "HDMI_CEC_29") (pintype "bidirectional"))
    )
    (net (code "117") (name "unconnected-(J1-LVDS_DDC_CLK-Pad35)") (class "Default")
      (node (ref "J1") (pin "35") (pinfunction "LVDS_DDC_CLK_35") (pintype "output"))
    )
    (net (code "118") (name "unconnected-(J1-LVDS_DDC_DAT-Pad33)") (class "Default")
      (node (ref "J1") (pin "33") (pinfunction "LVDS_DDC_DAT_33") (pintype "bidirectional"))
    )
    (net (code "119") (name "unconnected-(J1-LVDS_LCLK#-Pad176)") (class "Default")
      (node (ref "J1") (pin "176") (pinfunction "LVDS_LCLK#_176") (pintype "output"))
    )
    (net (code "120") (name "unconnected-(J1-LVDS_LCLK-Pad178)") (class "Default")
      (node (ref "J1") (pin "178") (pinfunction "LVDS_LCLK_178") (pintype "output"))
    )
    (net (code "121") (name "unconnected-(J1-LVDS_LTX0#-Pad200)") (class "Default")
      (node (ref "J1") (pin "200") (pinfunction "LVDS_LTX0#_200") (pintype "output"))
    )
    (net (code "122") (name "unconnected-(J1-LVDS_LTX0-Pad202)") (class "Default")
      (node (ref "J1") (pin "202") (pinfunction "LVDS_LTX0_202") (pintype "output"))
    )
    (net (code "123") (name "unconnected-(J1-LVDS_LTX1#-Pad194)") (class "Default")
      (node (ref "J1") (pin "194") (pinfunction "LVDS_LTX1#_194") (pintype "output"))
    )
    (net (code "124") (name "unconnected-(J1-LVDS_LTX1-Pad196)") (class "Default")
      (node (ref "J1") (pin "196") (pinfunction "LVDS_LTX1_196") (pintype "output"))
    )
    (net (code "125") (name "unconnected-(J1-LVDS_LTX2#-Pad188)") (class "Default")
      (node (ref "J1") (pin "188") (pinfunction "LVDS_LTX2#_188") (pintype "output"))
    )
    (net (code "126") (name "unconnected-(J1-LVDS_LTX2-Pad190)") (class "Default")
      (node (ref "J1") (pin "190") (pinfunction "LVDS_LTX2_190") (pintype "output"))
    )
    (net (code "127") (name "unconnected-(J1-LVDS_LTX3#-Pad182)") (class "Default")
      (node (ref "J1") (pin "182") (pinfunction "LVDS_LTX3#_182") (pintype "output"))
    )
    (net (code "128") (name "unconnected-(J1-LVDS_LTX3-Pad184)") (class "Default")
      (node (ref "J1") (pin "184") (pinfunction "LVDS_LTX3_184") (pintype "output"))
    )
    (net (code "129") (name "unconnected-(J1-LVDS_UCLK#-Pad169)") (class "Default")
      (node (ref "J1") (pin "169") (pinfunction "LVDS_UCLK#_169") (pintype "output"))
    )
    (net (code "130") (name "unconnected-(J1-LVDS_UCLK-Pad171)") (class "Default")
      (node (ref "J1") (pin "171") (pinfunction "LVDS_UCLK_171") (pintype "output"))
    )
    (net (code "131") (name "unconnected-(J1-LVDS_UTX0#-Pad193)") (class "Default")
      (node (ref "J1") (pin "193") (pinfunction "LVDS_UTX0#_193") (pintype "output"))
    )
    (net (code "132") (name "unconnected-(J1-LVDS_UTX0-Pad195)") (class "Default")
      (node (ref "J1") (pin "195") (pinfunction "LVDS_UTX0_195") (pintype "output"))
    )
    (net (code "133") (name "unconnected-(J1-LVDS_UTX1#-Pad187)") (class "Default")
      (node (ref "J1") (pin "187") (pinfunction "LVDS_UTX1#_187") (pintype "output"))
    )
    (net (code "134") (name "unconnected-(J1-LVDS_UTX1-Pad189)") (class "Default")
      (node (ref "J1") (pin "189") (pinfunction "LVDS_UTX1_189") (pintype "output"))
    )
    (net (code "135") (name "unconnected-(J1-LVDS_UTX2#-Pad181)") (class "Default")
      (node (ref "J1") (pin "181") (pinfunction "LVDS_UTX2#_181") (pintype "output"))
    )
    (net (code "136") (name "unconnected-(J1-LVDS_UTX2-Pad183)") (class "Default")
      (node (ref "J1") (pin "183") (pinfunction "LVDS_UTX2_183") (pintype "output"))
    )
    (net (code "137") (name "unconnected-(J1-LVDS_UTX3#-Pad175)") (class "Default")
      (node (ref "J1") (pin "175") (pinfunction "LVDS_UTX3#_175") (pintype "output"))
    )
    (net (code "138") (name "unconnected-(J1-LVDS_UTX3-Pad177)") (class "Default")
      (node (ref "J1") (pin "177") (pinfunction "LVDS_UTX3_177") (pintype "output"))
    )
    (net (code "139") (name "unconnected-(J1-OEM-Pad38)") (class "Default")
      (node (ref "J1") (pin "38") (pinfunction "OEM_38") (pintype "bidirectional"))
    )
    (net (code "140") (name "unconnected-(J1-OEM-Pad39)") (class "Default")
      (node (ref "J1") (pin "39") (pinfunction "OEM_39") (pintype "bidirectional"))
    )
    (net (code "141") (name "unconnected-(J1-OEM-Pad40)") (class "Default")
      (node (ref "J1") (pin "40") (pinfunction "OEM_40") (pintype "bidirectional"))
    )
    (net (code "142") (name "unconnected-(J1-OEM-Pad41)") (class "Default")
      (node (ref "J1") (pin "41") (pinfunction "OEM_41") (pintype "bidirectional"))
    )
    (net (code "143") (name "unconnected-(J1-OEM-Pad42)") (class "Default")
      (node (ref "J1") (pin "42") (pinfunction "OEM_42") (pintype "bidirectional"))
    )
    (net (code "144") (name "unconnected-(J1-OEM-Pad43)") (class "Default")
      (node (ref "J1") (pin "43") (pinfunction "OEM_43") (pintype "bidirectional"))
    )
    (net (code "145") (name "unconnected-(J1-OEM-Pad44)") (class "Default")
      (node (ref "J1") (pin "44") (pinfunction "OEM_44") (pintype "bidirectional"))
    )
    (net (code "146") (name "unconnected-(J1-OEM-Pad45)") (class "Default")
      (node (ref "J1") (pin "45") (pinfunction "OEM_45") (pintype "bidirectional"))
    )
    (net (code "147") (name "unconnected-(J1-PEX_RX8#-Pad91)") (class "Default")
      (node (ref "J1") (pin "91") (pinfunction "PEX_RX8#_91") (pintype "output+no_connect"))
    )
    (net (code "148") (name "unconnected-(J1-PEX_RX8-Pad93)") (class "Default")
      (node (ref "J1") (pin "93") (pinfunction "PEX_RX8_93") (pintype "output+no_connect"))
    )
    (net (code "149") (name "unconnected-(J1-PEX_RX9#-Pad85)") (class "Default")
      (node (ref "J1") (pin "85") (pinfunction "PEX_RX9#_85") (pintype "output+no_connect"))
    )
    (net (code "150") (name "unconnected-(J1-PEX_RX9-Pad87)") (class "Default")
      (node (ref "J1") (pin "87") (pinfunction "PEX_RX9_87") (pintype "output+no_connect"))
    )
    (net (code "151") (name "unconnected-(J1-PEX_RX10#-Pad79)") (class "Default")
      (node (ref "J1") (pin "79") (pinfunction "PEX_RX10#_79") (pintype "output+no_connect"))
    )
    (net (code "152") (name "unconnected-(J1-PEX_RX10-Pad81)") (class "Default")
      (node (ref "J1") (pin "81") (pinfunction "PEX_RX10_81") (pintype "output+no_connect"))
    )
    (net (code "153") (name "unconnected-(J1-PEX_RX11#-Pad73)") (class "Default")
      (node (ref "J1") (pin "73") (pinfunction "PEX_RX11#_73") (pintype "output+no_connect"))
    )
    (net (code "154") (name "unconnected-(J1-PEX_RX11-Pad75)") (class "Default")
      (node (ref "J1") (pin "75") (pinfunction "PEX_RX11_75") (pintype "output+no_connect"))
    )
    (net (code "155") (name "unconnected-(J1-PEX_RX12#-Pad67)") (class "Default")
      (node (ref "J1") (pin "67") (pinfunction "PEX_RX12#_67") (pintype "output+no_connect"))
    )
    (net (code "156") (name "unconnected-(J1-PEX_RX12-Pad69)") (class "Default")
      (node (ref "J1") (pin "69") (pinfunction "PEX_RX12_69") (pintype "output+no_connect"))
    )
    (net (code "157") (name "unconnected-(J1-PEX_RX13#-Pad61)") (class "Default")
      (node (ref "J1") (pin "61") (pinfunction "PEX_RX13#_61") (pintype "output+no_connect"))
    )
    (net (code "158") (name "unconnected-(J1-PEX_RX13-Pad63)") (class "Default")
      (node (ref "J1") (pin "63") (pinfunction "PEX_RX13_63") (pintype "output+no_connect"))
    )
    (net (code "159") (name "unconnected-(J1-PEX_RX14#-Pad55)") (class "Default")
      (node (ref "J1") (pin "55") (pinfunction "PEX_RX14#_55") (pintype "output+no_connect"))
    )
    (net (code "160") (name "unconnected-(J1-PEX_RX14-Pad57)") (class "Default")
      (node (ref "J1") (pin "57") (pinfunction "PEX_RX14_57") (pintype "output+no_connect"))
    )
    (net (code "161") (name "unconnected-(J1-PEX_RX15#-Pad49)") (class "Default")
      (node (ref "J1") (pin "49") (pinfunction "PEX_RX15#_49") (pintype "output+no_connect"))
    )
    (net (code "162") (name "unconnected-(J1-PEX_RX15-Pad51)") (class "Default")
      (node (ref "J1") (pin "51") (pinfunction "PEX_RX15_51") (pintype "output+no_connect"))
    )
    (net (code "163") (name "unconnected-(J1-PEX_STD_SW#-Pad19)") (class "Default")
      (node (ref "J1") (pin "19") (pinfunction "PEX_STD_SW#_19") (pintype "input"))
    )
    (net (code "164") (name "unconnected-(J1-PEX_TX8#-Pad90)") (class "Default")
      (node (ref "J1") (pin "90") (pinfunction "PEX_TX8#_90") (pintype "input"))
    )
    (net (code "165") (name "unconnected-(J1-PEX_TX8-Pad92)") (class "Default")
      (node (ref "J1") (pin "92") (pinfunction "PEX_TX8_92") (pintype "input"))
    )
    (net (code "166") (name "unconnected-(J1-PEX_TX9#-Pad84)") (class "Default")
      (node (ref "J1") (pin "84") (pinfunction "PEX_TX9#_84") (pintype "input"))
    )
    (net (code "167") (name "unconnected-(J1-PEX_TX9-Pad86)") (class "Default")
      (node (ref "J1") (pin "86") (pinfunction "PEX_TX9_86") (pintype "input"))
    )
    (net (code "168") (name "unconnected-(J1-PEX_TX10#-Pad78)") (class "Default")
      (node (ref "J1") (pin "78") (pinfunction "PEX_TX10#_78") (pintype "input"))
    )
    (net (code "169") (name "unconnected-(J1-PEX_TX10-Pad80)") (class "Default")
      (node (ref "J1") (pin "80") (pinfunction "PEX_TX10_80") (pintype "input"))
    )
    (net (code "170") (name "unconnected-(J1-PEX_TX11#-Pad72)") (class "Default")
      (node (ref "J1") (pin "72") (pinfunction "PEX_TX11#_72") (pintype "input"))
    )
    (net (code "171") (name "unconnected-(J1-PEX_TX11-Pad74)") (class "Default")
      (node (ref "J1") (pin "74") (pinfunction "PEX_TX11_74") (pintype "input"))
    )
    (net (code "172") (name "unconnected-(J1-PEX_TX12#-Pad66)") (class "Default")
      (node (ref "J1") (pin "66") (pinfunction "PEX_TX12#_66") (pintype "input"))
    )
    (net (code "173") (name "unconnected-(J1-PEX_TX12-Pad68)") (class "Default")
      (node (ref "J1") (pin "68") (pinfunction "PEX_TX12_68") (pintype "input"))
    )
    (net (code "174") (name "unconnected-(J1-PEX_TX13#-Pad60)") (class "Default")
      (node (ref "J1") (pin "60") (pinfunction "PEX_TX13#_60") (pintype "input"))
    )
    (net (code "175") (name "unconnected-(J1-PEX_TX13-Pad62)") (class "Default")
      (node (ref "J1") (pin "62") (pinfunction "PEX_TX13_62") (pintype "input"))
    )
    (net (code "176") (name "unconnected-(J1-PEX_TX14#-Pad54)") (class "Default")
      (node (ref "J1") (pin "54") (pinfunction "PEX_TX14#_54") (pintype "input"))
    )
    (net (code "177") (name "unconnected-(J1-PEX_TX14-Pad56)") (class "Default")
      (node (ref "J1") (pin "56") (pinfunction "PEX_TX14_56") (pintype "input"))
    )
    (net (code "178") (name "unconnected-(J1-PEX_TX15#-Pad48)") (class "Default")
      (node (ref "J1") (pin "48") (pinfunction "PEX_TX15#_48") (pintype "input"))
    )
    (net (code "179") (name "unconnected-(J1-PEX_TX15-Pad50)") (class "Default")
      (node (ref "J1") (pin "50") (pinfunction "PEX_TX15_50") (pintype "input"))
    )
    (net (code "180") (name "unconnected-(J1-PNL_BL_EN-Pad25)") (class "Default")
      (node (ref "J1") (pin "25") (pinfunction "PNL_BL_EN_25") (pintype "output"))
    )
    (net (code "181") (name "unconnected-(J1-PNL_BL_PWM-Pad27)") (class "Default")
      (node (ref "J1") (pin "27") (pinfunction "PNL_BL_PWM_27") (pintype "output"))
    )
    (net (code "182") (name "unconnected-(J1-PNL_PWR_EN-Pad23)") (class "Default")
      (node (ref "J1") (pin "23") (pinfunction "PNL_PWR_EN_23") (pintype "output"))
    )
    (net (code "183") (name "unconnected-(J1-PRSNT_L#-Pad281)") (class "Default")
      (node (ref "J1") (pin "281") (pinfunction "PRSNT_L#_281") (pintype "output"))
    )
    (net (code "184") (name "unconnected-(J1-PRSNT_R#-Pad2)") (class "Default")
      (node (ref "J1") (pin "2") (pinfunction "PRSNT_R#_2") (pintype "output"))
    )
    (net (code "185") (name "unconnected-(J1-RSVD-Pad10)") (class "Default")
      (node (ref "J1") (pin "10") (pinfunction "RSVD_10") (pintype "bidirectional"))
    )
    (net (code "186") (name "unconnected-(J1-RSVD-Pad12)") (class "Default")
      (node (ref "J1") (pin "12") (pinfunction "RSVD_12") (pintype "bidirectional"))
    )
    (net (code "187") (name "unconnected-(J1-RSVD-Pad14)") (class "Default")
      (node (ref "J1") (pin "14") (pinfunction "RSVD_14") (pintype "bidirectional"))
    )
    (net (code "188") (name "unconnected-(J1-RSVD-Pad16)") (class "Default")
      (node (ref "J1") (pin "16") (pinfunction "RSVD_16") (pintype "bidirectional"))
    )
    (net (code "189") (name "unconnected-(J1-RSVD-Pad159)") (class "Default")
      (node (ref "J1") (pin "159") (pinfunction "RSVD_159") (pintype "bidirectional"))
    )
    (net (code "190") (name "unconnected-(J1-RSVD-Pad161)") (class "Default")
      (node (ref "J1") (pin "161") (pinfunction "RSVD_161") (pintype "bidirectional"))
    )
    (net (code "191") (name "unconnected-(J1-RSVD-Pad163)") (class "Default")
      (node (ref "J1") (pin "163") (pinfunction "RSVD_163") (pintype "bidirectional"))
    )
    (net (code "192") (name "unconnected-(J1-RSVD-Pad165)") (class "Default")
      (node (ref "J1") (pin "165") (pinfunction "RSVD_165") (pintype "bidirectional"))
    )
    (net (code "193") (name "unconnected-(J1-RSVD-Pad167)") (class "Default")
      (node (ref "J1") (pin "167") (pinfunction "RSVD_167") (pintype "bidirectional"))
    )
    (net (code "194") (name "unconnected-(J1-RSVD-Pad227)") (class "Default")
      (node (ref "J1") (pin "227") (pinfunction "RSVD_227") (pintype "bidirectional"))
    )
    (net (code "195") (name "unconnected-(J1-RSVD-Pad229)") (class "Default")
      (node (ref "J1") (pin "229") (pinfunction "RSVD_229") (pintype "bidirectional"))
    )
    (net (code "196") (name "unconnected-(J1-RSVD-Pad231)") (class "Default")
      (node (ref "J1") (pin "231") (pinfunction "RSVD_231") (pintype "bidirectional"))
    )
    (net (code "197") (name "unconnected-(J1-RSVD-Pad233)") (class "Default")
      (node (ref "J1") (pin "233") (pinfunction "RSVD_233") (pintype "bidirectional"))
    )
    (net (code "198") (name "unconnected-(J1-RSVD-Pad235)") (class "Default")
      (node (ref "J1") (pin "235") (pinfunction "RSVD_235") (pintype "bidirectional"))
    )
    (net (code "199") (name "unconnected-(J1-RSVD-Pad237)") (class "Default")
      (node (ref "J1") (pin "237") (pinfunction "RSVD_237") (pintype "bidirectional"))
    )
    (net (code "200") (name "unconnected-(J1-RSVD-Pad238)") (class "Default")
      (node (ref "J1") (pin "238") (pinfunction "RSVD_238") (pintype "bidirectional"))
    )
    (net (code "201") (name "unconnected-(J1-RSVD-Pad239)") (class "Default")
      (node (ref "J1") (pin "239") (pinfunction "RSVD_239") (pintype "bidirectional"))
    )
    (net (code "202") (name "unconnected-(J1-RSVD-Pad240)") (class "Default")
      (node (ref "J1") (pin "240") (pinfunction "RSVD_240") (pintype "bidirectional"))
    )
    (net (code "203") (name "unconnected-(J1-RSVD-Pad241)") (class "Default")
      (node (ref "J1") (pin "241") (pinfunction "RSVD_241") (pintype "bidirectional"))
    )
    (net (code "204") (name "unconnected-(J1-RSVD-Pad242)") (class "Default")
      (node (ref "J1") (pin "242") (pinfunction "RSVD_242") (pintype "bidirectional"))
    )
    (net (code "205") (name "unconnected-(J1-RSVD-Pad243)") (class "Default")
      (node (ref "J1") (pin "243") (pinfunction "RSVD_243") (pintype "bidirectional"))
    )
    (net (code "206") (name "unconnected-(J1-RSVD-Pad245)") (class "Default")
      (node (ref "J1") (pin "245") (pinfunction "RSVD_245") (pintype "bidirectional"))
    )
    (net (code "207") (name "unconnected-(J1-RSVD-Pad247)") (class "Default")
      (node (ref "J1") (pin "247") (pinfunction "RSVD_247") (pintype "bidirectional"))
    )
    (net (code "208") (name "unconnected-(J1-RSVD-Pad249)") (class "Default")
      (node (ref "J1") (pin "249") (pinfunction "RSVD_249") (pintype "bidirectional"))
    )
    (net (code "209") (name "unconnected-(J1-VGA_BLUE-Pad172)") (class "Default")
      (node (ref "J1") (pin "172") (pinfunction "VGA_BLUE_172") (pintype "output"))
    )
    (net (code "210") (name "unconnected-(J1-VGA_DDC_CLK-Pad160)") (class "Default")
      (node (ref "J1") (pin "160") (pinfunction "VGA_DDC_CLK_160") (pintype "output"))
    )
    (net (code "211") (name "unconnected-(J1-VGA_DDC_DAT-Pad158)") (class "Default")
      (node (ref "J1") (pin "158") (pinfunction "VGA_DDC_DAT_158") (pintype "bidirectional"))
    )
    (net (code "212") (name "unconnected-(J1-VGA_DISABLE#-Pad21)") (class "Default")
      (node (ref "J1") (pin "21") (pinfunction "VGA_DISABLE#_21") (pintype "input"))
    )
    (net (code "213") (name "unconnected-(J1-VGA_GREEN-Pad170)") (class "Default")
      (node (ref "J1") (pin "170") (pinfunction "VGA_GREEN_170") (pintype "output"))
    )
    (net (code "214") (name "unconnected-(J1-VGA_HSYNC-Pad164)") (class "Default")
      (node (ref "J1") (pin "164") (pinfunction "VGA_HSYNC_164") (pintype "output"))
    )
    (net (code "215") (name "unconnected-(J1-VGA_RED-Pad168)") (class "Default")
      (node (ref "J1") (pin "168") (pinfunction "VGA_RED_168") (pintype "output"))
    )
    (net (code "216") (name "unconnected-(J1-VGA_VSYNC-Pad162)") (class "Default")
      (node (ref "J1") (pin "162") (pinfunction "VGA_VSYNC_162") (pintype "output"))
    )
    (net (code "217") (name "unconnected-(J1-WAKE#-Pad4)") (class "Default")
      (node (ref "J1") (pin "4") (pinfunction "WAKE#_4") (pintype "output"))
    )
    (net (code "218") (name "unconnected-(U2-12V_FAN-PadPL4)") (class "Default")
      (node (ref "U2") (pin "PL4") (pinfunction "12V_FAN_PL4") (pintype "unspecified"))
    )
    (net (code "219") (name "unconnected-(U2-DDS_CLK-PadPL2)") (class "Default")
      (node (ref "U2") (pin "PL2") (pinfunction "DDS_CLK_PL2") (pintype "bidirectional"))
    )
    (net (code "220") (name "unconnected-(U2-DDS_SDA-PadPK1)") (class "Default")
      (node (ref "U2") (pin "PK1") (pinfunction "DDS_SDA_PK1") (pintype "input"))
    )
    (net (code "221") (name "unconnected-(U2-Fan0_PWM-PadPL5)") (class "Default")
      (node (ref "U2") (pin "PL5") (pinfunction "Fan0_PWM_PL5") (pintype "input"))
    )
    (net (code "222") (name "unconnected-(U2-Fan0_SPEED-PadPH2)") (class "Default")
      (node (ref "U2") (pin "PH2") (pinfunction "Fan0_SPEED_PH2") (pintype "output"))
    )
    (net (code "223") (name "unconnected-(U2-Fan1_PWM-PadPK5)") (class "Default")
      (node (ref "U2") (pin "PK5") (pinfunction "Fan1_PWM_PK5") (pintype "input"))
    )
    (net (code "224") (name "unconnected-(U2-Fan1_SPEED-PadPJ2)") (class "Default")
      (node (ref "U2") (pin "PJ2") (pinfunction "Fan1_SPEED_PJ2") (pintype "output"))
    )
    (net (code "225") (name "unconnected-(U2-GPIO0_EC-PadPG1)") (class "Default")
      (node (ref "U2") (pin "PG1") (pinfunction "GPIO0_EC_PG1") (pintype "unspecified"))
    )
    (net (code "226") (name "unconnected-(U2-GPIO1_EC-PadPH1)") (class "Default")
      (node (ref "U2") (pin "PH1") (pinfunction "GPIO1_EC_PH1") (pintype "unspecified"))
    )
    (net (code "227") (name "unconnected-(U2-GPIO2_EC-PadSA2)") (class "Default")
      (node (ref "U2") (pin "SA2") (pinfunction "GPIO2_EC_SA2") (pintype "unspecified"))
    )
    (net (code "228") (name "unconnected-(U2-GPIO3_EC-PadSL7)") (class "Default")
      (node (ref "U2") (pin "SL7") (pinfunction "GPIO3_EC_SL7") (pintype "unspecified"))
    )
    (net (code "229") (name "unconnected-(U2-I2C_CLK_ALW-PadPC3)") (class "Default")
      (node (ref "U2") (pin "PC3") (pinfunction "I2C_CLK_ALW_PC3") (pintype "bidirectional"))
    )
    (net (code "230") (name "unconnected-(U2-I2C_DAT_ALW-PadPD3)") (class "Default")
      (node (ref "U2") (pin "PD3") (pinfunction "I2C_DAT_ALW_PD3") (pintype "bidirectional"))
    )
    (net (code "231") (name "unconnected-(U2-I2C_INT_ALW-PadPF2)") (class "Default")
      (node (ref "U2") (pin "PF2") (pinfunction "I2C_INT_ALW_PF2") (pintype "bidirectional"))
    )
    (net (code "232") (name "unconnected-(U2-I2C_INT_VS-PadPG2)") (class "Default")
      (node (ref "U2") (pin "PG2") (pinfunction "I2C_INT_VS_PG2") (pintype "unspecified"))
    )
    (net (code "233") (name "unconnected-(U2-ID1-PadSL2)") (class "Default")
      (node (ref "U2") (pin "SL2") (pinfunction "ID1_SL2") (pintype "unspecified"))
    )
    (net (code "234") (name "unconnected-(U2-PNL_BL_EN-PadSL4)") (class "Default")
      (node (ref "U2") (pin "SL4") (pinfunction "PNL_BL_EN_SL4") (pintype "unspecified"))
    )
    (net (code "235") (name "unconnected-(U2-USB+-PadPJ3)") (class "Default")
      (node (ref "U2") (pin "PJ3") (pinfunction "USB+_PJ3") (pintype "bidirectional"))
    )
    (net (code "236") (name "unconnected-(U2-USB--PadPK3)") (class "Default")
      (node (ref "U2") (pin "PK3") (pinfunction "USB-_PK3") (pintype "bidirectional"))
    )
    (net (code "237") (name "unconnected-(U2-VADP_GPU-PadPA1)") (class "Default")
      (node (ref "U2") (pin "PA1") (pinfunction "VADP_GPU_PA1") (pintype "unspecified+no_connect"))
    )
    (net (code "238") (name "unconnected-(U2-VADP_GPU-PadPA2)") (class "Default")
      (node (ref "U2") (pin "PA2") (pinfunction "VADP_GPU_PA2") (pintype "unspecified+no_connect"))
    )
    (net (code "239") (name "unconnected-(U2-VADP_GPU-PadPB1)") (class "Default")
      (node (ref "U2") (pin "PB1") (pinfunction "VADP_GPU_PB1") (pintype "unspecified+no_connect"))
    )
    (net (code "240") (name "unconnected-(U2-VADP_GPU-PadPB2)") (class "Default")
      (node (ref "U2") (pin "PB2") (pinfunction "VADP_GPU_PB2") (pintype "unspecified+no_connect"))
    )
    (net (code "241") (name "unconnected-(U2-VADP_GPU-PadPC1)") (class "Default")
      (node (ref "U2") (pin "PC1") (pinfunction "VADP_GPU_PC1") (pintype "unspecified+no_connect"))
    )
    (net (code "242") (name "unconnected-(U2-VADP_GPU-PadPC2)") (class "Default")
      (node (ref "U2") (pin "PC2") (pinfunction "VADP_GPU_PC2") (pintype "unspecified+no_connect"))
    )
  )
)
